# p128control.net
KiCad netlist of a schematic drawn in EAGLE
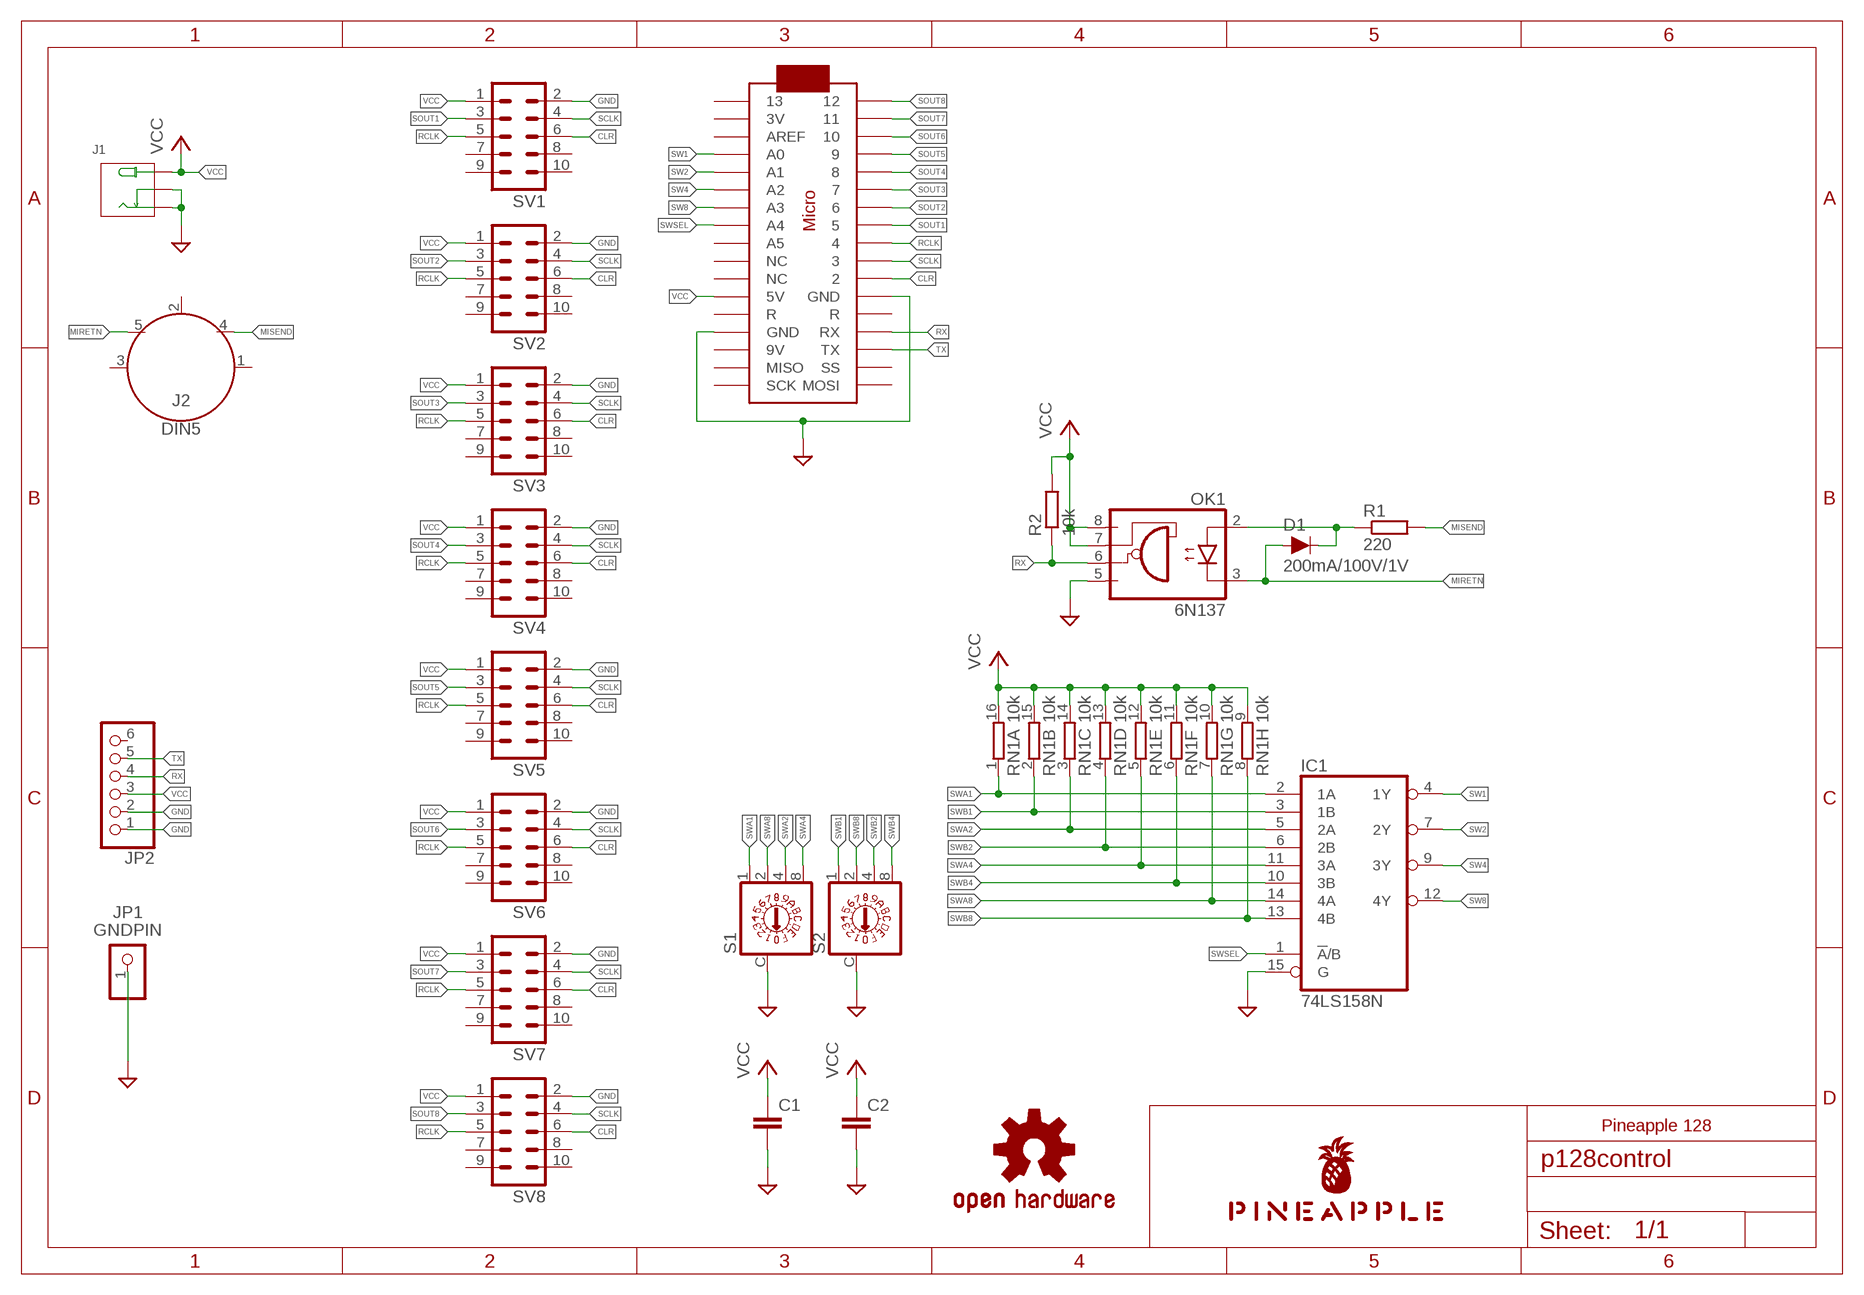
[diagram p0: schematic, sheet 1]

(export (version "E")
  (design (tool "Eeschema 10.0.6"))
  (components
    (comp (ref "C1")
      (value "C-EU025-024X044")
      (footprint "eagle-import:C025-024X044")
      (libsource (lib "eagle-import") (part "C-EU025-024X044"))
    )
    (comp (ref "C2")
      (value "C-EU025-024X044")
      (footprint "eagle-import:C025-024X044")
      (libsource (lib "eagle-import") (part "C-EU025-024X044"))
    )
    (comp (ref "D1")
      (value "200mA/100V/1V")
      (footprint "eagle-import:DIODE-1N4148")
      (libsource (lib "eagle-import") (part "DIODE-1N4148"))
    )
    (comp (ref "IC1")
      (value "74LS158N")
      (footprint "eagle-import:DIL16")
      (libsource (lib "eagle-import") (part "74158NLS"))
    )
    (comp (ref "J1")
      (value "JACK-DC-005'DC-005'")
      (footprint "eagle-import:3P-L14.2_W11.0_H9.0MM")
      (libsource (lib "eagle-import") (part "JACK-DC-005'DC-005'"))
    )
    (comp (ref "J2")
      (value "DIN5")
      (footprint "eagle-import:DIN5-RA-PTH")
      (libsource (lib "eagle-import") (part "DIN5"))
    )
    (comp (ref "JP1")
      (value "GNDPIN")
      (footprint "eagle-import:1X01")
      (libsource (lib "eagle-import") (part "PINHD-1X1"))
    )
    (comp (ref "JP2")
      (value "PINHD-1X6")
      (footprint "eagle-import:1X06")
      (libsource (lib "eagle-import") (part "PINHD-1X6"))
    )
    (comp (ref "LOGO1")
      (value "OSHW-LOGOS-COPPER")
      (footprint "eagle-import:OSHW-LOGO-S_COPPER")
      (libsource (lib "eagle-import") (part "OSHW-LOGOS-COPPER"))
    )
    (comp (ref "OK1")
      (value "6N137")
      (footprint "eagle-import:DIL08")
      (libsource (lib "eagle-import") (part "6N137"))
    )
    (comp (ref "R1")
      (value "220")
      (footprint "eagle-import:0204_5")
      (libsource (lib "eagle-import") (part "R-EU_0204/5"))
    )
    (comp (ref "R2")
      (value "10k")
      (footprint "eagle-import:0204_5")
      (libsource (lib "eagle-import") (part "R-EU_0204/5"))
    )
    (comp (ref "RN1")
      (value "10k")
      (footprint "eagle-import:DIL16")
      (libsource (lib "eagle-import") (part "8R-N"))
    )
    (comp (ref "S1")
      (value "A1353HEX")
      (footprint "eagle-import:A1353HEX")
      (libsource (lib "eagle-import") (part "A1353HEX"))
    )
    (comp (ref "S2")
      (value "A1353HEX")
      (footprint "eagle-import:A1353HEX")
      (libsource (lib "eagle-import") (part "A1353HEX"))
    )
    (comp (ref "SV1")
      (value "ML10")
      (footprint "eagle-import:ML10")
      (libsource (lib "eagle-import") (part "ML10"))
    )
    (comp (ref "SV2")
      (value "ML10")
      (footprint "eagle-import:ML10")
      (libsource (lib "eagle-import") (part "ML10"))
    )
    (comp (ref "SV3")
      (value "ML10")
      (footprint "eagle-import:ML10")
      (libsource (lib "eagle-import") (part "ML10"))
    )
    (comp (ref "SV4")
      (value "ML10")
      (footprint "eagle-import:ML10")
      (libsource (lib "eagle-import") (part "ML10"))
    )
    (comp (ref "SV5")
      (value "ML10")
      (footprint "eagle-import:ML10")
      (libsource (lib "eagle-import") (part "ML10"))
    )
    (comp (ref "SV6")
      (value "ML10")
      (footprint "eagle-import:ML10")
      (libsource (lib "eagle-import") (part "ML10"))
    )
    (comp (ref "SV7")
      (value "ML10")
      (footprint "eagle-import:ML10")
      (libsource (lib "eagle-import") (part "ML10"))
    )
    (comp (ref "SV8")
      (value "ML10")
      (footprint "eagle-import:ML10")
      (libsource (lib "eagle-import") (part "ML10"))
    )
    (comp (ref "U$1")
      (value "PINEAPPLE450_SILK")
      (footprint "eagle-import:PINEAPPLE450_SILK")
      (libsource (lib "eagle-import") (part "PINEAPPLE450_SILK"))
    )
    (comp (ref "U$2")
      (value "ARDUINOMICRO")
      (footprint "eagle-import:ARDUINOMICRO")
      (libsource (lib "eagle-import") (part "ARDUINOMICRO"))
    )
  )
  (nets
    (net (code "1") (name "CLR") (class "Default")
      (node (ref "SV1") (pin "6") (pinfunction "6_6") (pintype "passive"))
      (node (ref "SV2") (pin "6") (pinfunction "6_6") (pintype "passive"))
      (node (ref "SV3") (pin "6") (pinfunction "6_6") (pintype "passive"))
      (node (ref "SV4") (pin "6") (pinfunction "6_6") (pintype "passive"))
      (node (ref "SV5") (pin "6") (pinfunction "6_6") (pintype "passive"))
      (node (ref "SV6") (pin "6") (pinfunction "6_6") (pintype "passive"))
      (node (ref "SV7") (pin "6") (pinfunction "6_6") (pintype "passive"))
      (node (ref "SV8") (pin "6") (pinfunction "6_6") (pintype "passive"))
      (node (ref "U$2") (pin "P$11") (pinfunction "2_P$11") (pintype "bidirectional"))
    )
    (net (code "2") (name "GND") (class "Default")
      (node (ref "C1") (pin "2") (pinfunction "2_2") (pintype "passive"))
      (node (ref "C2") (pin "2") (pinfunction "2_2") (pintype "passive"))
      (node (ref "IC1") (pin "15") (pinfunction "G_15") (pintype "input"))
      (node (ref "J1") (pin "-1") (pinfunction "-_-1") (pintype "bidirectional"))
      (node (ref "J1") (pin "-2") (pinfunction "CDN_-2") (pintype "bidirectional"))
      (node (ref "JP1") (pin "1") (pinfunction "1_1") (pintype "passive"))
      (node (ref "JP2") (pin "1") (pinfunction "1_1") (pintype "passive"))
      (node (ref "JP2") (pin "2") (pinfunction "2_2") (pintype "passive"))
      (node (ref "OK1") (pin "5") (pinfunction "GND_5") (pintype "passive"))
      (node (ref "S1") (pin "C") (pinfunction "C_C") (pintype "passive"))
      (node (ref "S2") (pin "C") (pinfunction "C_C") (pintype "passive"))
      (node (ref "SV1") (pin "2") (pinfunction "2_2") (pintype "passive"))
      (node (ref "SV2") (pin "2") (pinfunction "2_2") (pintype "passive"))
      (node (ref "SV3") (pin "2") (pinfunction "2_2") (pintype "passive"))
      (node (ref "SV4") (pin "2") (pinfunction "2_2") (pintype "passive"))
      (node (ref "SV5") (pin "2") (pinfunction "2_2") (pintype "passive"))
      (node (ref "SV6") (pin "2") (pinfunction "2_2") (pintype "passive"))
      (node (ref "SV7") (pin "2") (pinfunction "2_2") (pintype "passive"))
      (node (ref "SV8") (pin "2") (pinfunction "2_2") (pintype "passive"))
      (node (ref "U$2") (pin "P$12") (pinfunction "GND_P$12") (pintype "bidirectional"))
      (node (ref "U$2") (pin "P$21") (pinfunction "GND_P$21") (pintype "bidirectional"))
    )
    (net (code "3") (name "MIRETN") (class "Default")
      (node (ref "D1") (pin "A") (pinfunction "A_A") (pintype "passive"))
      (node (ref "J2") (pin "5") (pinfunction "5_5") (pintype "bidirectional"))
      (node (ref "OK1") (pin "3") (pinfunction "C_3") (pintype "passive"))
    )
    (net (code "4") (name "MISEND") (class "Default")
      (node (ref "J2") (pin "4") (pinfunction "4_4") (pintype "bidirectional"))
      (node (ref "R1") (pin "2") (pinfunction "2_2") (pintype "passive"))
    )
    (net (code "5") (name "Net-(OK1-A)") (class "Default")
      (node (ref "D1") (pin "C") (pinfunction "C_C") (pintype "passive"))
      (node (ref "OK1") (pin "2") (pinfunction "A_2") (pintype "passive"))
      (node (ref "R1") (pin "1") (pinfunction "1_1") (pintype "passive"))
    )
    (net (code "6") (name "RCLK") (class "Default")
      (node (ref "SV1") (pin "5") (pinfunction "5_5") (pintype "passive"))
      (node (ref "SV2") (pin "5") (pinfunction "5_5") (pintype "passive"))
      (node (ref "SV3") (pin "5") (pinfunction "5_5") (pintype "passive"))
      (node (ref "SV4") (pin "5") (pinfunction "5_5") (pintype "passive"))
      (node (ref "SV5") (pin "5") (pinfunction "5_5") (pintype "passive"))
      (node (ref "SV6") (pin "5") (pinfunction "5_5") (pintype "passive"))
      (node (ref "SV7") (pin "5") (pinfunction "5_5") (pintype "passive"))
      (node (ref "SV8") (pin "5") (pinfunction "5_5") (pintype "passive"))
      (node (ref "U$2") (pin "P$9") (pinfunction "4_P$9") (pintype "bidirectional"))
    )
    (net (code "7") (name "RX") (class "Default")
      (node (ref "JP2") (pin "4") (pinfunction "4_4") (pintype "passive"))
      (node (ref "OK1") (pin "6") (pinfunction "VO_6") (pintype "passive"))
      (node (ref "R2") (pin "1") (pinfunction "1_1") (pintype "passive"))
      (node (ref "U$2") (pin "P$14") (pinfunction "RX_P$14") (pintype "bidirectional"))
    )
    (net (code "8") (name "SCLK") (class "Default")
      (node (ref "SV1") (pin "4") (pinfunction "4_4") (pintype "passive"))
      (node (ref "SV2") (pin "4") (pinfunction "4_4") (pintype "passive"))
      (node (ref "SV3") (pin "4") (pinfunction "4_4") (pintype "passive"))
      (node (ref "SV4") (pin "4") (pinfunction "4_4") (pintype "passive"))
      (node (ref "SV5") (pin "4") (pinfunction "4_4") (pintype "passive"))
      (node (ref "SV6") (pin "4") (pinfunction "4_4") (pintype "passive"))
      (node (ref "SV7") (pin "4") (pinfunction "4_4") (pintype "passive"))
      (node (ref "SV8") (pin "4") (pinfunction "4_4") (pintype "passive"))
      (node (ref "U$2") (pin "P$10") (pinfunction "3_P$10") (pintype "bidirectional"))
    )
    (net (code "9") (name "SOUT1") (class "Default")
      (node (ref "SV1") (pin "3") (pinfunction "3_3") (pintype "passive"))
      (node (ref "U$2") (pin "P$8") (pinfunction "5_P$8") (pintype "bidirectional"))
    )
    (net (code "10") (name "SOUT2") (class "Default")
      (node (ref "SV2") (pin "3") (pinfunction "3_3") (pintype "passive"))
      (node (ref "U$2") (pin "P$7") (pinfunction "6_P$7") (pintype "bidirectional"))
    )
    (net (code "11") (name "SOUT3") (class "Default")
      (node (ref "SV3") (pin "3") (pinfunction "3_3") (pintype "passive"))
      (node (ref "U$2") (pin "P$6") (pinfunction "7_P$6") (pintype "bidirectional"))
    )
    (net (code "12") (name "SOUT4") (class "Default")
      (node (ref "SV4") (pin "3") (pinfunction "3_3") (pintype "passive"))
      (node (ref "U$2") (pin "P$5") (pinfunction "8_P$5") (pintype "bidirectional"))
    )
    (net (code "13") (name "SOUT5") (class "Default")
      (node (ref "SV5") (pin "3") (pinfunction "3_3") (pintype "passive"))
      (node (ref "U$2") (pin "P$4") (pinfunction "9_P$4") (pintype "bidirectional"))
    )
    (net (code "14") (name "SOUT6") (class "Default")
      (node (ref "SV6") (pin "3") (pinfunction "3_3") (pintype "passive"))
      (node (ref "U$2") (pin "P$3") (pinfunction "10_P$3") (pintype "bidirectional"))
    )
    (net (code "15") (name "SOUT7") (class "Default")
      (node (ref "SV7") (pin "3") (pinfunction "3_3") (pintype "passive"))
      (node (ref "U$2") (pin "P$2") (pinfunction "11_P$2") (pintype "bidirectional"))
    )
    (net (code "16") (name "SOUT8") (class "Default")
      (node (ref "SV8") (pin "3") (pinfunction "3_3") (pintype "passive"))
      (node (ref "U$2") (pin "P$1") (pinfunction "12_P$1") (pintype "bidirectional"))
    )
    (net (code "17") (name "SW1") (class "Default")
      (node (ref "IC1") (pin "4") (pinfunction "1Y_4") (pintype "output"))
      (node (ref "U$2") (pin "P$31") (pinfunction "A0_P$31") (pintype "bidirectional"))
    )
    (net (code "18") (name "SW2") (class "Default")
      (node (ref "IC1") (pin "7") (pinfunction "2Y_7") (pintype "output"))
      (node (ref "U$2") (pin "P$30") (pinfunction "A1_P$30") (pintype "bidirectional"))
    )
    (net (code "19") (name "SW4") (class "Default")
      (node (ref "IC1") (pin "9") (pinfunction "3Y_9") (pintype "output"))
      (node (ref "U$2") (pin "P$29") (pinfunction "A2_P$29") (pintype "bidirectional"))
    )
    (net (code "20") (name "SW8") (class "Default")
      (node (ref "IC1") (pin "12") (pinfunction "4Y_12") (pintype "output"))
      (node (ref "U$2") (pin "P$28") (pinfunction "A3_P$28") (pintype "bidirectional"))
    )
    (net (code "21") (name "SWA1") (class "Default")
      (node (ref "IC1") (pin "2") (pinfunction "1A_2") (pintype "input"))
      (node (ref "RN1") (pin "1") (pinfunction "1_1") (pintype "passive"))
      (node (ref "S1") (pin "1") (pinfunction "1_1") (pintype "passive"))
    )
    (net (code "22") (name "SWA2") (class "Default")
      (node (ref "IC1") (pin "5") (pinfunction "2A_5") (pintype "input"))
      (node (ref "RN1") (pin "3") (pinfunction "1_3") (pintype "passive"))
      (node (ref "S1") (pin "4") (pinfunction "4_4") (pintype "passive"))
    )
    (net (code "23") (name "SWA4") (class "Default")
      (node (ref "IC1") (pin "11") (pinfunction "3A_11") (pintype "input"))
      (node (ref "RN1") (pin "5") (pinfunction "1_5") (pintype "passive"))
      (node (ref "S1") (pin "8") (pinfunction "8_8") (pintype "passive"))
    )
    (net (code "24") (name "SWA8") (class "Default")
      (node (ref "IC1") (pin "14") (pinfunction "4A_14") (pintype "input"))
      (node (ref "RN1") (pin "7") (pinfunction "1_7") (pintype "passive"))
      (node (ref "S1") (pin "2") (pinfunction "2_2") (pintype "passive"))
    )
    (net (code "25") (name "SWB1") (class "Default")
      (node (ref "IC1") (pin "3") (pinfunction "1B_3") (pintype "input"))
      (node (ref "RN1") (pin "2") (pinfunction "1_2") (pintype "passive"))
      (node (ref "S2") (pin "1") (pinfunction "1_1") (pintype "passive"))
    )
    (net (code "26") (name "SWB2") (class "Default")
      (node (ref "IC1") (pin "6") (pinfunction "2B_6") (pintype "input"))
      (node (ref "RN1") (pin "4") (pinfunction "1_4") (pintype "passive"))
      (node (ref "S2") (pin "4") (pinfunction "4_4") (pintype "passive"))
    )
    (net (code "27") (name "SWB4") (class "Default")
      (node (ref "IC1") (pin "10") (pinfunction "3B_10") (pintype "input"))
      (node (ref "RN1") (pin "6") (pinfunction "1_6") (pintype "passive"))
      (node (ref "S2") (pin "8") (pinfunction "8_8") (pintype "passive"))
    )
    (net (code "28") (name "SWB8") (class "Default")
      (node (ref "IC1") (pin "13") (pinfunction "4B_13") (pintype "input"))
      (node (ref "RN1") (pin "8") (pinfunction "1_8") (pintype "passive"))
      (node (ref "S2") (pin "2") (pinfunction "2_2") (pintype "passive"))
    )
    (net (code "29") (name "SWSEL") (class "Default")
      (node (ref "IC1") (pin "1") (pinfunction "~{A}/B_1") (pintype "input"))
      (node (ref "U$2") (pin "P$27") (pinfunction "A4_P$27") (pintype "bidirectional"))
    )
    (net (code "30") (name "TX") (class "Default")
      (node (ref "JP2") (pin "5") (pinfunction "5_5") (pintype "passive"))
      (node (ref "U$2") (pin "P$15") (pinfunction "TX_P$15") (pintype "bidirectional"))
    )
    (net (code "31") (name "VCC") (class "Default")
      (node (ref "C1") (pin "1") (pinfunction "1_1") (pintype "passive"))
      (node (ref "C2") (pin "1") (pinfunction "1_1") (pintype "passive"))
      (node (ref "J1") (pin "+") (pinfunction "+_+") (pintype "bidirectional"))
      (node (ref "JP2") (pin "3") (pinfunction "3_3") (pintype "passive"))
      (node (ref "OK1") (pin "7") (pinfunction "VE_7") (pintype "passive"))
      (node (ref "OK1") (pin "8") (pinfunction "VCC_8") (pintype "passive"))
      (node (ref "R2") (pin "2") (pinfunction "2_2") (pintype "passive"))
      (node (ref "RN1") (pin "10") (pinfunction "2_10") (pintype "passive"))
      (node (ref "RN1") (pin "11") (pinfunction "2_11") (pintype "passive"))
      (node (ref "RN1") (pin "12") (pinfunction "2_12") (pintype "passive"))
      (node (ref "RN1") (pin "13") (pinfunction "2_13") (pintype "passive"))
      (node (ref "RN1") (pin "14") (pinfunction "2_14") (pintype "passive"))
      (node (ref "RN1") (pin "15") (pinfunction "2_15") (pintype "passive"))
      (node (ref "RN1") (pin "16") (pinfunction "2_16") (pintype "passive"))
      (node (ref "RN1") (pin "9") (pinfunction "2_9") (pintype "passive"))
      (node (ref "SV1") (pin "1") (pinfunction "1_1") (pintype "passive"))
      (node (ref "SV2") (pin "1") (pinfunction "1_1") (pintype "passive"))
      (node (ref "SV3") (pin "1") (pinfunction "1_1") (pintype "passive"))
      (node (ref "SV4") (pin "1") (pinfunction "1_1") (pintype "passive"))
      (node (ref "SV5") (pin "1") (pinfunction "1_1") (pintype "passive"))
      (node (ref "SV6") (pin "1") (pinfunction "1_1") (pintype "passive"))
      (node (ref "SV7") (pin "1") (pinfunction "1_1") (pintype "passive"))
      (node (ref "SV8") (pin "1") (pinfunction "1_1") (pintype "passive"))
      (node (ref "U$2") (pin "P$23") (pinfunction "5V_P$23") (pintype "bidirectional"))
    )
    (net (code "32") (name "unconnected-(J2-Pad1)") (class "Default")
      (node (ref "J2") (pin "1") (pinfunction "1_1") (pintype "bidirectional"))
    )
    (net (code "33") (name "unconnected-(J2-Pad2)") (class "Default")
      (node (ref "J2") (pin "2") (pinfunction "2_2") (pintype "bidirectional"))
    )
    (net (code "34") (name "unconnected-(J2-Pad3)") (class "Default")
      (node (ref "J2") (pin "3") (pinfunction "3_3") (pintype "bidirectional"))
    )
    (net (code "35") (name "unconnected-(JP2-Pad6)") (class "Default")
      (node (ref "JP2") (pin "6") (pinfunction "6_6") (pintype "passive"))
    )
    (net (code "36") (name "unconnected-(SV1-Pad7)") (class "Default")
      (node (ref "SV1") (pin "7") (pinfunction "7_7") (pintype "passive"))
    )
    (net (code "37") (name "unconnected-(SV1-Pad8)") (class "Default")
      (node (ref "SV1") (pin "8") (pinfunction "8_8") (pintype "passive"))
    )
    (net (code "38") (name "unconnected-(SV1-Pad9)") (class "Default")
      (node (ref "SV1") (pin "9") (pinfunction "9_9") (pintype "passive"))
    )
    (net (code "39") (name "unconnected-(SV1-Pad10)") (class "Default")
      (node (ref "SV1") (pin "10") (pinfunction "10_10") (pintype "passive"))
    )
    (net (code "40") (name "unconnected-(SV2-Pad7)") (class "Default")
      (node (ref "SV2") (pin "7") (pinfunction "7_7") (pintype "passive"))
    )
    (net (code "41") (name "unconnected-(SV2-Pad8)") (class "Default")
      (node (ref "SV2") (pin "8") (pinfunction "8_8") (pintype "passive"))
    )
    (net (code "42") (name "unconnected-(SV2-Pad9)") (class "Default")
      (node (ref "SV2") (pin "9") (pinfunction "9_9") (pintype "passive"))
    )
    (net (code "43") (name "unconnected-(SV2-Pad10)") (class "Default")
      (node (ref "SV2") (pin "10") (pinfunction "10_10") (pintype "passive"))
    )
    (net (code "44") (name "unconnected-(SV3-Pad7)") (class "Default")
      (node (ref "SV3") (pin "7") (pinfunction "7_7") (pintype "passive"))
    )
    (net (code "45") (name "unconnected-(SV3-Pad8)") (class "Default")
      (node (ref "SV3") (pin "8") (pinfunction "8_8") (pintype "passive"))
    )
    (net (code "46") (name "unconnected-(SV3-Pad9)") (class "Default")
      (node (ref "SV3") (pin "9") (pinfunction "9_9") (pintype "passive"))
    )
    (net (code "47") (name "unconnected-(SV3-Pad10)") (class "Default")
      (node (ref "SV3") (pin "10") (pinfunction "10_10") (pintype "passive"))
    )
    (net (code "48") (name "unconnected-(SV4-Pad7)") (class "Default")
      (node (ref "SV4") (pin "7") (pinfunction "7_7") (pintype "passive"))
    )
    (net (code "49") (name "unconnected-(SV4-Pad8)") (class "Default")
      (node (ref "SV4") (pin "8") (pinfunction "8_8") (pintype "passive"))
    )
    (net (code "50") (name "unconnected-(SV4-Pad9)") (class "Default")
      (node (ref "SV4") (pin "9") (pinfunction "9_9") (pintype "passive"))
    )
    (net (code "51") (name "unconnected-(SV4-Pad10)") (class "Default")
      (node (ref "SV4") (pin "10") (pinfunction "10_10") (pintype "passive"))
    )
    (net (code "52") (name "unconnected-(SV5-Pad7)") (class "Default")
      (node (ref "SV5") (pin "7") (pinfunction "7_7") (pintype "passive"))
    )
    (net (code "53") (name "unconnected-(SV5-Pad8)") (class "Default")
      (node (ref "SV5") (pin "8") (pinfunction "8_8") (pintype "passive"))
    )
    (net (code "54") (name "unconnected-(SV5-Pad9)") (class "Default")
      (node (ref "SV5") (pin "9") (pinfunction "9_9") (pintype "passive"))
    )
    (net (code "55") (name "unconnected-(SV5-Pad10)") (class "Default")
      (node (ref "SV5") (pin "10") (pinfunction "10_10") (pintype "passive"))
    )
    (net (code "56") (name "unconnected-(SV6-Pad7)") (class "Default")
      (node (ref "SV6") (pin "7") (pinfunction "7_7") (pintype "passive"))
    )
    (net (code "57") (name "unconnected-(SV6-Pad8)") (class "Default")
      (node (ref "SV6") (pin "8") (pinfunction "8_8") (pintype "passive"))
    )
    (net (code "58") (name "unconnected-(SV6-Pad9)") (class "Default")
      (node (ref "SV6") (pin "9") (pinfunction "9_9") (pintype "passive"))
    )
    (net (code "59") (name "unconnected-(SV6-Pad10)") (class "Default")
      (node (ref "SV6") (pin "10") (pinfunction "10_10") (pintype "passive"))
    )
    (net (code "60") (name "unconnected-(SV7-Pad7)") (class "Default")
      (node (ref "SV7") (pin "7") (pinfunction "7_7") (pintype "passive"))
    )
    (net (code "61") (name "unconnected-(SV7-Pad8)") (class "Default")
      (node (ref "SV7") (pin "8") (pinfunction "8_8") (pintype "passive"))
    )
    (net (code "62") (name "unconnected-(SV7-Pad9)") (class "Default")
      (node (ref "SV7") (pin "9") (pinfunction "9_9") (pintype "passive"))
    )
    (net (code "63") (name "unconnected-(SV7-Pad10)") (class "Default")
      (node (ref "SV7") (pin "10") (pinfunction "10_10") (pintype "passive"))
    )
    (net (code "64") (name "unconnected-(SV8-Pad7)") (class "Default")
      (node (ref "SV8") (pin "7") (pinfunction "7_7") (pintype "passive"))
    )
    (net (code "65") (name "unconnected-(SV8-Pad8)") (class "Default")
      (node (ref "SV8") (pin "8") (pinfunction "8_8") (pintype "passive"))
    )
    (net (code "66") (name "unconnected-(SV8-Pad9)") (class "Default")
      (node (ref "SV8") (pin "9") (pinfunction "9_9") (pintype "passive"))
    )
    (net (code "67") (name "unconnected-(SV8-Pad10)") (class "Default")
      (node (ref "SV8") (pin "10") (pinfunction "10_10") (pintype "passive"))
    )
    (net (code "68") (name "unconnected-(U$2-3V-PadP$33)") (class "Default")
      (node (ref "U$2") (pin "P$33") (pinfunction "3V_P$33") (pintype "bidirectional"))
    )
    (net (code "69") (name "unconnected-(U$2-9V-PadP$20)") (class "Default")
      (node (ref "U$2") (pin "P$20") (pinfunction "9V_P$20") (pintype "bidirectional"))
    )
    (net (code "70") (name "unconnected-(U$2-13-PadP$34)") (class "Default")
      (node (ref "U$2") (pin "P$34") (pinfunction "13_P$34") (pintype "bidirectional"))
    )
    (net (code "71") (name "unconnected-(U$2-A5-PadP$26)") (class "Default")
      (node (ref "U$2") (pin "P$26") (pinfunction "A5_P$26") (pintype "bidirectional"))
    )
    (net (code "72") (name "unconnected-(U$2-AREF-PadP$32)") (class "Default")
      (node (ref "U$2") (pin "P$32") (pinfunction "AREF_P$32") (pintype "bidirectional"))
    )
    (net (code "73") (name "unconnected-(U$2-MISO-PadP$19)") (class "Default")
      (node (ref "U$2") (pin "P$19") (pinfunction "MISO_P$19") (pintype "bidirectional"))
    )
    (net (code "74") (name "unconnected-(U$2-MOSI-PadP$17)") (class "Default")
      (node (ref "U$2") (pin "P$17") (pinfunction "MOSI_P$17") (pintype "bidirectional"))
    )
    (net (code "75") (name "unconnected-(U$2-NC-PadP$24)") (class "Default")
      (node (ref "U$2") (pin "P$24") (pinfunction "NC_P$24") (pintype "bidirectional"))
    )
    (net (code "76") (name "unconnected-(U$2-NC-PadP$25)") (class "Default")
      (node (ref "U$2") (pin "P$25") (pinfunction "NC_P$25") (pintype "bidirectional"))
    )
    (net (code "77") (name "unconnected-(U$2-R-PadP$13)") (class "Default")
      (node (ref "U$2") (pin "P$13") (pinfunction "R_P$13") (pintype "bidirectional"))
    )
    (net (code "78") (name "unconnected-(U$2-R-PadP$22)") (class "Default")
      (node (ref "U$2") (pin "P$22") (pinfunction "R_P$22") (pintype "bidirectional"))
    )
    (net (code "79") (name "unconnected-(U$2-SCK-PadP$18)") (class "Default")
      (node (ref "U$2") (pin "P$18") (pinfunction "SCK_P$18") (pintype "bidirectional"))
    )
    (net (code "80") (name "unconnected-(U$2-SS-PadP$16)") (class "Default")
      (node (ref "U$2") (pin "P$16") (pinfunction "SS_P$16") (pintype "bidirectional"))
    )
  )
)
